# Ethernet.net
KiCad netlist of a schematic drawn in Altium Designer
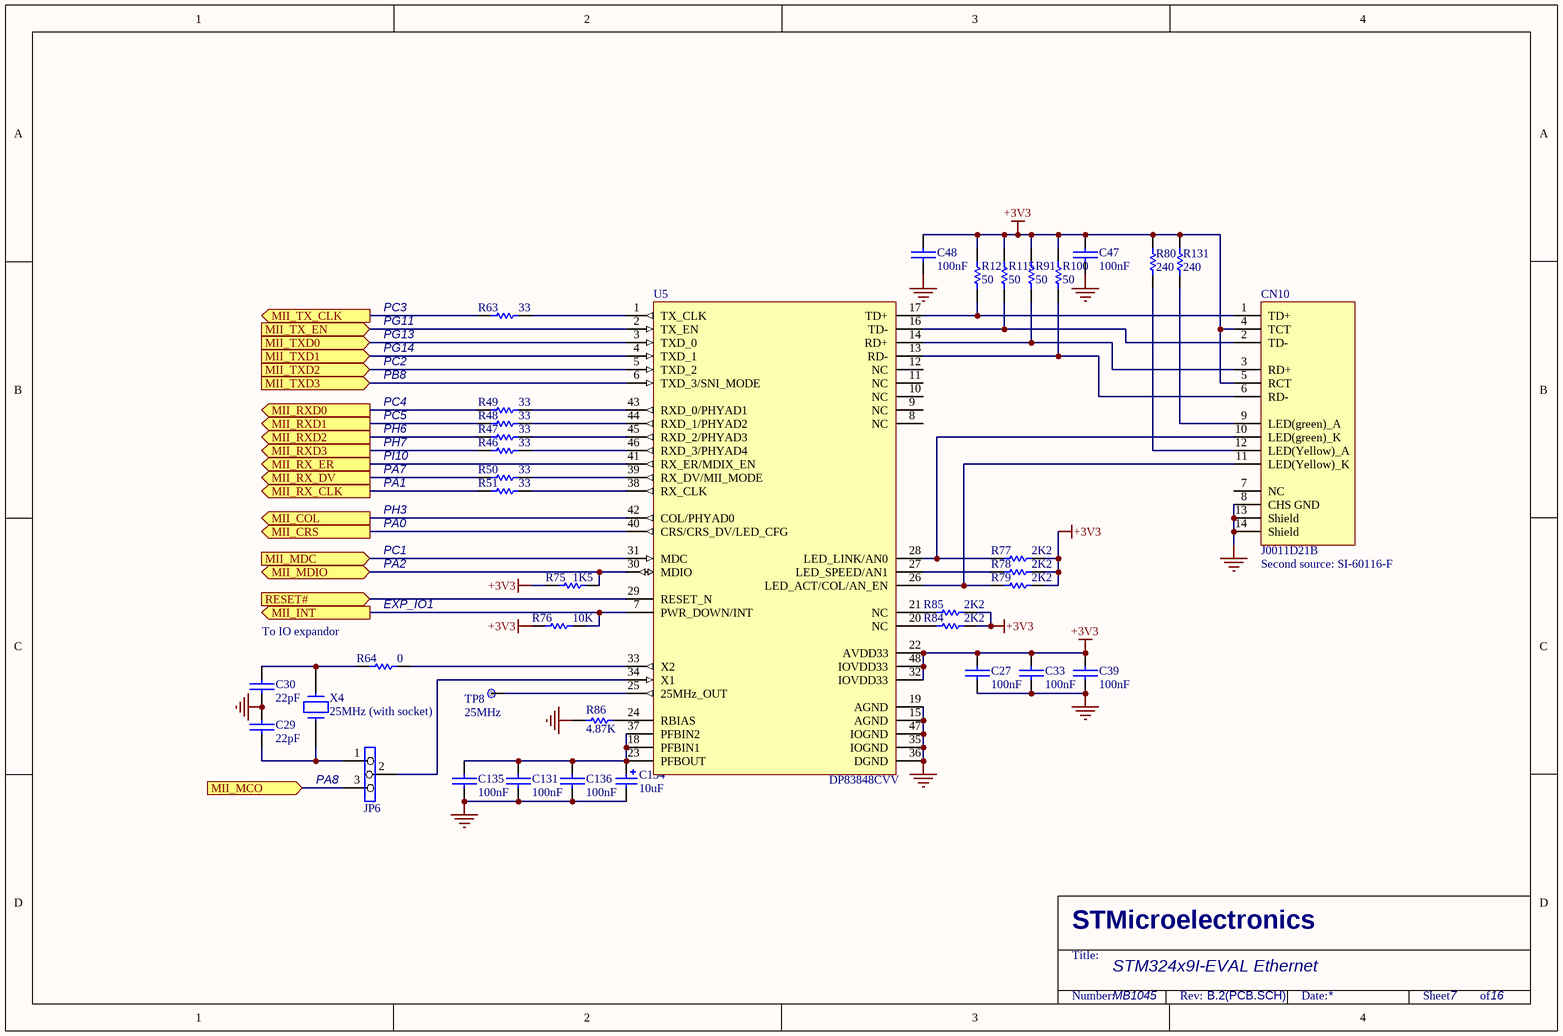
[diagram p0: Ethernet.SchDoc]

(export (version "E")
  (design (tool "Eeschema 10.0.6"))
  (components
    (comp (ref "C27")
      (value "100nF")
      (footprint "0603C")
      (description "Capacitor")
      (libsource (lib "*") (part "CAP"))
    )
    (comp (ref "C29")
      (value "22pF")
      (footprint "0603C")
      (description "Capacitor")
      (libsource (lib "*") (part "CAP"))
    )
    (comp (ref "C30")
      (value "22pF")
      (footprint "0603C")
      (description "Capacitor")
      (libsource (lib "*") (part "CAP"))
    )
    (comp (ref "C33")
      (value "100nF")
      (footprint "0603C")
      (description "Capacitor")
      (libsource (lib "*") (part "CAP"))
    )
    (comp (ref "C39")
      (value "100nF")
      (footprint "0603C")
      (description "Capacitor")
      (libsource (lib "*") (part "CAP"))
    )
    (comp (ref "C47")
      (value "100nF")
      (footprint "0603C")
      (description "Capacitor")
      (libsource (lib "*") (part "CAP"))
    )
    (comp (ref "C48")
      (value "100nF")
      (footprint "0603C")
      (description "Capacitor")
      (libsource (lib "*") (part "CAP"))
    )
    (comp (ref "C131")
      (value "100nF")
      (footprint "0603C")
      (description "Capacitor")
      (libsource (lib "*") (part "CAP"))
    )
    (comp (ref "C134")
      (value "10uF")
      (footprint "TAN-A")
      (description "Polarized Capacitor (Radial)")
      (fields (field (name "PUBLISHER") "Altium Limited"))
      (libsource (lib "Miscellaneous Devices") (part "Cap Pol1"))
    )
    (comp (ref "C135")
      (value "100nF")
      (footprint "0603C")
      (description "Capacitor")
      (libsource (lib "*") (part "CAP"))
    )
    (comp (ref "C136")
      (value "100nF")
      (footprint "0603C")
      (description "Capacitor")
      (libsource (lib "*") (part "CAP"))
    )
    (comp (ref "CN10")
      (value "J0011D21B")
      (footprint "RJ45_J0011D01BNL")
      (libsource (lib "MB784") (part "J0011D21B"))
    )
    (comp (ref "JP6") (value "~") (footprint "SIP3") (libsource (lib "STR910_SCHLIB") (part "Jumper3")))
    (comp (ref "R46")
      (value "33")
      (footprint "0603R")
      (description "Resistor")
      (fields (field (name "PUBLISHER") "Altium Limited"))
      (libsource (lib "Miscellaneous Devices") (part "Res1"))
    )
    (comp (ref "R47")
      (value "33")
      (footprint "0603R")
      (description "Resistor")
      (fields (field (name "PUBLISHER") "Altium Limited"))
      (libsource (lib "Miscellaneous Devices") (part "Res1"))
    )
    (comp (ref "R48")
      (value "33")
      (footprint "0603R")
      (description "Resistor")
      (fields (field (name "PUBLISHER") "Altium Limited"))
      (libsource (lib "Miscellaneous Devices") (part "Res1"))
    )
    (comp (ref "R49")
      (value "33")
      (footprint "0603R")
      (description "Resistor")
      (fields (field (name "PUBLISHER") "Altium Limited"))
      (libsource (lib "Miscellaneous Devices") (part "Res1"))
    )
    (comp (ref "R50")
      (value "33")
      (footprint "0603R")
      (description "Resistor")
      (fields (field (name "PUBLISHER") "Altium Limited"))
      (libsource (lib "Miscellaneous Devices") (part "Res1"))
    )
    (comp (ref "R51")
      (value "33")
      (footprint "0603R")
      (description "Resistor")
      (fields (field (name "PUBLISHER") "Altium Limited"))
      (libsource (lib "Miscellaneous Devices") (part "Res1"))
    )
    (comp (ref "R63")
      (value "33")
      (footprint "0603R")
      (description "Resistor")
      (fields (field (name "PUBLISHER") "Altium Limited"))
      (libsource (lib "Miscellaneous Devices") (part "Res1"))
    )
    (comp (ref "R64")
      (value "0")
      (footprint "0603R")
      (description "Resistor")
      (fields (field (name "PUBLISHER") "Altium Limited"))
      (libsource (lib "Miscellaneous Devices") (part "Res1"))
    )
    (comp (ref "R75")
      (value "1K5")
      (footprint "0603R")
      (description "Resistor")
      (fields (field (name "PUBLISHER") "Altium Limited"))
      (libsource (lib "Miscellaneous Devices") (part "Res1"))
    )
    (comp (ref "R76")
      (value "10K")
      (footprint "0603R")
      (description "Resistor")
      (fields (field (name "PUBLISHER") "Altium Limited"))
      (libsource (lib "Miscellaneous Devices") (part "Res1"))
    )
    (comp (ref "R77")
      (value "2K2")
      (footprint "0603R")
      (description "Resistor")
      (fields (field (name "PUBLISHER") "Altium Limited"))
      (libsource (lib "Miscellaneous Devices") (part "Res1"))
    )
    (comp (ref "R78")
      (value "2K2")
      (footprint "0603R")
      (description "Resistor")
      (fields (field (name "PUBLISHER") "Altium Limited"))
      (libsource (lib "Miscellaneous Devices") (part "Res1"))
    )
    (comp (ref "R79")
      (value "2K2")
      (footprint "0603R")
      (description "Resistor")
      (fields (field (name "PUBLISHER") "Altium Limited"))
      (libsource (lib "Miscellaneous Devices") (part "Res1"))
    )
    (comp (ref "R80")
      (value "240")
      (footprint "0603R")
      (description "Resistor")
      (fields (field (name "PUBLISHER") "Altium Limited"))
      (libsource (lib "Miscellaneous Devices") (part "Res1"))
    )
    (comp (ref "R84")
      (value "2K2")
      (footprint "0603R")
      (description "Resistor")
      (fields (field (name "PUBLISHER") "Altium Limited"))
      (libsource (lib "Miscellaneous Devices") (part "Res1"))
    )
    (comp (ref "R85")
      (value "2K2")
      (footprint "0603R")
      (description "Resistor")
      (fields (field (name "PUBLISHER") "Altium Limited"))
      (libsource (lib "Miscellaneous Devices") (part "Res1"))
    )
    (comp (ref "R86")
      (value "4.87K")
      (footprint "0603R")
      (description "Resistor")
      (fields (field (name "PUBLISHER") "Altium Limited"))
      (libsource (lib "Miscellaneous Devices") (part "Res1"))
    )
    (comp (ref "R91")
      (value "50")
      (footprint "0603R")
      (description "Resistor")
      (fields (field (name "PUBLISHER") "Altium Limited"))
      (libsource (lib "Miscellaneous Devices") (part "Res1"))
    )
    (comp (ref "R100")
      (value "50")
      (footprint "0603R")
      (description "Resistor")
      (fields (field (name "PUBLISHER") "Altium Limited"))
      (libsource (lib "Miscellaneous Devices") (part "Res1"))
    )
    (comp (ref "R115")
      (value "50")
      (footprint "0603R")
      (description "Resistor")
      (fields (field (name "PUBLISHER") "Altium Limited"))
      (libsource (lib "Miscellaneous Devices") (part "Res1"))
    )
    (comp (ref "R121")
      (value "50")
      (footprint "0603R")
      (description "Resistor")
      (fields (field (name "PUBLISHER") "Altium Limited"))
      (libsource (lib "Miscellaneous Devices") (part "Res1"))
    )
    (comp (ref "R131")
      (value "240")
      (footprint "0603R")
      (description "Resistor")
      (fields (field (name "PUBLISHER") "Altium Limited"))
      (libsource (lib "Miscellaneous Devices") (part "Res1"))
    )
    (comp (ref "TP8") (value "25MHz") (footprint "TP") (libsource (lib "*") (part "TP")))
    (comp (ref "U5")
      (value "DP83848CVV")
      (footprint "LQFP48_0R5_9X9")
      (libsource (lib "MB784") (part "DP83848CVV"))
    )
    (comp (ref "X4")
      (value "25MHz (with socket)")
      (footprint "XTAL_socket")
      (description "Crystal")
      (libsource (lib "*") (part "CRYSTAL"))
    )
  )
  (nets
    (net (code "1") (name "+3V3") (class "Default")
      (node (ref "C27") (pin "1") (pinfunction "1_1") (pintype "passive"))
      (node (ref "C33") (pin "2") (pinfunction "2_2") (pintype "passive"))
      (node (ref "C39") (pin "2") (pinfunction "2_2") (pintype "passive"))
      (node (ref "C47") (pin "2") (pinfunction "2_2") (pintype "passive"))
      (node (ref "C48") (pin "2") (pinfunction "2_2") (pintype "passive"))
      (node (ref "CN10") (pin "4") (pinfunction "TCT_4") (pintype "passive"))
      (node (ref "CN10") (pin "5") (pinfunction "RCT_5") (pintype "passive"))
      (node (ref "R100") (pin "1") (pinfunction "1_1") (pintype "passive"))
      (node (ref "R115") (pin "1") (pinfunction "1_1") (pintype "passive"))
      (node (ref "R121") (pin "1") (pinfunction "1_1") (pintype "passive"))
      (node (ref "R131") (pin "2") (pinfunction "2_2") (pintype "passive"))
      (node (ref "R75") (pin "2") (pinfunction "2_2") (pintype "passive"))
      (node (ref "R76") (pin "1") (pinfunction "1_1") (pintype "passive"))
      (node (ref "R77") (pin "2") (pinfunction "2_2") (pintype "passive"))
      (node (ref "R78") (pin "2") (pinfunction "2_2") (pintype "passive"))
      (node (ref "R79") (pin "2") (pinfunction "2_2") (pintype "passive"))
      (node (ref "R80") (pin "2") (pinfunction "2_2") (pintype "passive"))
      (node (ref "R84") (pin "2") (pinfunction "2_2") (pintype "passive"))
      (node (ref "R85") (pin "2") (pinfunction "2_2") (pintype "passive"))
      (node (ref "R91") (pin "1") (pinfunction "1_1") (pintype "passive"))
      (node (ref "U5") (pin "22") (pinfunction "AVDD33_22") (pintype "passive"))
      (node (ref "U5") (pin "32") (pinfunction "IOVDD33_32") (pintype "passive"))
      (node (ref "U5") (pin "48") (pinfunction "IOVDD33_48") (pintype "passive"))
    )
    (net (code "2") (name "/MII_COL") (class "Default")
      (node (ref "U5") (pin "42") (pinfunction "COL/PHYAD0_42") (pintype "output"))
    )
    (net (code "3") (name "/MII_CRS") (class "Default")
      (node (ref "U5") (pin "40") (pinfunction "CRS/CRS_DV/LED_CFG_40") (pintype "output"))
    )
    (net (code "4") (name "/MII_INT") (class "Default")
      (node (ref "R76") (pin "2") (pinfunction "2_2") (pintype "passive"))
      (node (ref "U5") (pin "7") (pinfunction "PWR_DOWN/INT_7") (pintype "passive"))
    )
    (net (code "5") (name "/MII_MCO") (class "Default") (node (ref "JP6") (pin "3") (pintype "passive")))
    (net (code "6") (name "/MII_MDC") (class "Default")
      (node (ref "U5") (pin "31") (pinfunction "MDC_31") (pintype "input"))
    )
    (net (code "7") (name "/MII_MDIO") (class "Default")
      (node (ref "R75") (pin "1") (pinfunction "1_1") (pintype "passive"))
      (node (ref "U5") (pin "30") (pinfunction "MDIO_30") (pintype "bidirectional"))
    )
    (net (code "8") (name "/MII_RXD0") (class "Default")
      (node (ref "R49") (pin "2") (pinfunction "2_2") (pintype "passive"))
    )
    (net (code "9") (name "/MII_RXD1") (class "Default")
      (node (ref "R48") (pin "2") (pinfunction "2_2") (pintype "passive"))
    )
    (net (code "10") (name "/MII_RXD2") (class "Default")
      (node (ref "R47") (pin "2") (pinfunction "2_2") (pintype "passive"))
    )
    (net (code "11") (name "/MII_RXD3") (class "Default")
      (node (ref "R46") (pin "2") (pinfunction "2_2") (pintype "passive"))
    )
    (net (code "12") (name "/MII_RX_CLK") (class "Default")
      (node (ref "R51") (pin "2") (pinfunction "2_2") (pintype "passive"))
    )
    (net (code "13") (name "/MII_RX_DV") (class "Default")
      (node (ref "R50") (pin "2") (pinfunction "2_2") (pintype "passive"))
    )
    (net (code "14") (name "/MII_RX_ER") (class "Default")
      (node (ref "U5") (pin "41") (pinfunction "RX_ER/MDIX_EN_41") (pintype "output"))
    )
    (net (code "15") (name "/MII_TXD0") (class "Default")
      (node (ref "U5") (pin "3") (pinfunction "TXD_0_3") (pintype "input"))
    )
    (net (code "16") (name "/MII_TXD1") (class "Default")
      (node (ref "U5") (pin "4") (pinfunction "TXD_1_4") (pintype "input"))
    )
    (net (code "17") (name "/MII_TXD2") (class "Default")
      (node (ref "U5") (pin "5") (pinfunction "TXD_2_5") (pintype "input"))
    )
    (net (code "18") (name "/MII_TXD3") (class "Default")
      (node (ref "U5") (pin "6") (pinfunction "TXD_3/SNI_MODE_6") (pintype "input"))
    )
    (net (code "19") (name "/MII_TX_CLK") (class "Default")
      (node (ref "R63") (pin "2") (pinfunction "2_2") (pintype "passive"))
    )
    (net (code "20") (name "/MII_TX_EN") (class "Default")
      (node (ref "U5") (pin "2") (pinfunction "TX_EN_2") (pintype "input"))
    )
    (net (code "21") (name "/RESET#") (class "Default")
      (node (ref "U5") (pin "29") (pinfunction "RESET_N_29") (pintype "passive"))
    )
    (net (code "22") (name "GND") (class "Default")
      (node (ref "C131") (pin "1") (pinfunction "1_1") (pintype "passive"))
      (node (ref "C134") (pin "2") (pinfunction "2_2") (pintype "passive"))
      (node (ref "C135") (pin "2") (pinfunction "2_2") (pintype "passive"))
      (node (ref "C136") (pin "1") (pinfunction "1_1") (pintype "passive"))
      (node (ref "C27") (pin "2") (pinfunction "2_2") (pintype "passive"))
      (node (ref "C29") (pin "2") (pinfunction "2_2") (pintype "passive"))
      (node (ref "C30") (pin "1") (pinfunction "1_1") (pintype "passive"))
      (node (ref "C33") (pin "1") (pinfunction "1_1") (pintype "passive"))
      (node (ref "C39") (pin "1") (pinfunction "1_1") (pintype "passive"))
      (node (ref "C47") (pin "1") (pinfunction "1_1") (pintype "passive"))
      (node (ref "C48") (pin "1") (pinfunction "1_1") (pintype "passive"))
      (node (ref "CN10") (pin "13") (pinfunction "Shield_13") (pintype "passive"))
      (node (ref "CN10") (pin "14") (pinfunction "Shield_14") (pintype "passive"))
      (node (ref "CN10") (pin "8") (pinfunction "CHS_GND_8") (pintype "passive"))
      (node (ref "R86") (pin "1") (pinfunction "1_1") (pintype "passive"))
      (node (ref "U5") (pin "15") (pinfunction "AGND_15") (pintype "passive"))
      (node (ref "U5") (pin "19") (pinfunction "AGND_19") (pintype "passive"))
      (node (ref "U5") (pin "35") (pinfunction "IOGND_35") (pintype "passive"))
      (node (ref "U5") (pin "36") (pinfunction "DGND_36") (pintype "passive"))
      (node (ref "U5") (pin "47") (pinfunction "IOGND_47") (pintype "passive"))
    )
    (net (code "23") (name "Net-(C29-Pad1)") (class "Default")
      (node (ref "C29") (pin "1") (pinfunction "1_1") (pintype "passive"))
      (node (ref "JP6") (pin "1") (pintype "passive"))
      (node (ref "X4") (pin "1") (pinfunction "1_1") (pintype "passive"))
    )
    (net (code "24") (name "Net-(C30-Pad2)") (class "Default")
      (node (ref "C30") (pin "2") (pinfunction "2_2") (pintype "passive"))
      (node (ref "R64") (pin "2") (pinfunction "2_2") (pintype "passive"))
      (node (ref "X4") (pin "2") (pinfunction "2_2") (pintype "passive"))
    )
    (net (code "25") (name "Net-(CN10-LED(Yellow)_A)") (class "Default")
      (node (ref "CN10") (pin "12") (pinfunction "LED(Yellow)_A_12") (pintype "passive"))
      (node (ref "R80") (pin "1") (pinfunction "1_1") (pintype "passive"))
    )
    (net (code "26") (name "Net-(CN10-LED(Yellow)_K)") (class "Default")
      (node (ref "CN10") (pin "11") (pinfunction "LED(Yellow)_K_11") (pintype "passive"))
      (node (ref "R79") (pin "1") (pinfunction "1_1") (pintype "passive"))
      (node (ref "U5") (pin "26") (pinfunction "LED_ACT/COL/AN_EN_26") (pintype "passive"))
    )
    (net (code "27") (name "Net-(CN10-LED(green)_A)") (class "Default")
      (node (ref "CN10") (pin "9") (pinfunction "LED(green)_A_9") (pintype "passive"))
      (node (ref "R131") (pin "1") (pinfunction "1_1") (pintype "passive"))
    )
    (net (code "28") (name "Net-(CN10-LED(green)_K)") (class "Default")
      (node (ref "CN10") (pin "10") (pinfunction "LED(green)_K_10") (pintype "passive"))
      (node (ref "R77") (pin "1") (pinfunction "1_1") (pintype "passive"))
      (node (ref "U5") (pin "28") (pinfunction "LED_LINK/AN0_28") (pintype "passive"))
    )
    (net (code "29") (name "Net-(CN10-RD+)") (class "Default")
      (node (ref "CN10") (pin "3") (pinfunction "RD+_3") (pintype "passive"))
      (node (ref "R91") (pin "2") (pinfunction "2_2") (pintype "passive"))
      (node (ref "U5") (pin "14") (pinfunction "RD+_14") (pintype "passive"))
    )
    (net (code "30") (name "Net-(CN10-RD-)") (class "Default")
      (node (ref "CN10") (pin "6") (pinfunction "RD-_6") (pintype "passive"))
      (node (ref "R100") (pin "2") (pinfunction "2_2") (pintype "passive"))
      (node (ref "U5") (pin "13") (pinfunction "RD-_13") (pintype "passive"))
    )
    (net (code "31") (name "Net-(CN10-TD+)") (class "Default")
      (node (ref "CN10") (pin "1") (pinfunction "TD+_1") (pintype "passive"))
      (node (ref "R121") (pin "2") (pinfunction "2_2") (pintype "passive"))
      (node (ref "U5") (pin "17") (pinfunction "TD+_17") (pintype "passive"))
    )
    (net (code "32") (name "Net-(CN10-TD-)") (class "Default")
      (node (ref "CN10") (pin "2") (pinfunction "TD-_2") (pintype "passive"))
      (node (ref "R115") (pin "2") (pinfunction "2_2") (pintype "passive"))
      (node (ref "U5") (pin "16") (pinfunction "TD-_16") (pintype "passive"))
    )
    (net (code "33") (name "Net-(R84-Pad1)") (class "Default")
      (node (ref "R84") (pin "1") (pinfunction "1_1") (pintype "passive"))
      (node (ref "U5") (pin "20") (pinfunction "NC_20") (pintype "passive"))
    )
    (net (code "34") (name "Net-(R85-Pad1)") (class "Default")
      (node (ref "R85") (pin "1") (pinfunction "1_1") (pintype "passive"))
      (node (ref "U5") (pin "21") (pinfunction "NC_21") (pintype "passive"))
    )
    (net (code "35") (name "Net-(U5-25MHz_OUT)") (class "Default")
      (node (ref "TP8") (pin "1") (pinfunction "1_1") (pintype "passive"))
      (node (ref "U5") (pin "25") (pinfunction "25MHz_OUT_25") (pintype "output"))
    )
    (net (code "36") (name "Net-(U5-LED_SPEED{slash}AN1)") (class "Default")
      (node (ref "R78") (pin "1") (pinfunction "1_1") (pintype "passive"))
      (node (ref "U5") (pin "27") (pinfunction "LED_SPEED/AN1_27") (pintype "passive"))
    )
    (net (code "37") (name "Net-(U5-PFBIN1)") (class "Default")
      (node (ref "C131") (pin "2") (pinfunction "2_2") (pintype "passive"))
      (node (ref "C134") (pin "1") (pinfunction "1_1") (pintype "passive"))
      (node (ref "C135") (pin "1") (pinfunction "1_1") (pintype "passive"))
      (node (ref "C136") (pin "2") (pinfunction "2_2") (pintype "passive"))
      (node (ref "U5") (pin "18") (pinfunction "PFBIN1_18") (pintype "passive"))
      (node (ref "U5") (pin "23") (pinfunction "PFBOUT_23") (pintype "passive"))
      (node (ref "U5") (pin "37") (pinfunction "PFBIN2_37") (pintype "passive"))
    )
    (net (code "38") (name "Net-(U5-RBIAS)") (class "Default")
      (node (ref "R86") (pin "2") (pinfunction "2_2") (pintype "passive"))
      (node (ref "U5") (pin "24") (pinfunction "RBIAS_24") (pintype "passive"))
    )
    (net (code "39") (name "Net-(U5-RXD_0{slash}PHYAD1)") (class "Default")
      (node (ref "R49") (pin "1") (pinfunction "1_1") (pintype "passive"))
      (node (ref "U5") (pin "43") (pinfunction "RXD_0/PHYAD1_43") (pintype "output"))
    )
    (net (code "40") (name "Net-(U5-RXD_1{slash}PHYAD2)") (class "Default")
      (node (ref "R48") (pin "1") (pinfunction "1_1") (pintype "passive"))
      (node (ref "U5") (pin "44") (pinfunction "RXD_1/PHYAD2_44") (pintype "output"))
    )
    (net (code "41") (name "Net-(U5-RXD_2{slash}PHYAD3)") (class "Default")
      (node (ref "R47") (pin "1") (pinfunction "1_1") (pintype "passive"))
      (node (ref "U5") (pin "45") (pinfunction "RXD_2/PHYAD3_45") (pintype "output"))
    )
    (net (code "42") (name "Net-(U5-RXD_3{slash}PHYAD4)") (class "Default")
      (node (ref "R46") (pin "1") (pinfunction "1_1") (pintype "passive"))
      (node (ref "U5") (pin "46") (pinfunction "RXD_3/PHYAD4_46") (pintype "output"))
    )
    (net (code "43") (name "Net-(U5-RX_CLK)") (class "Default")
      (node (ref "R51") (pin "1") (pinfunction "1_1") (pintype "passive"))
      (node (ref "U5") (pin "38") (pinfunction "RX_CLK_38") (pintype "output"))
    )
    (net (code "44") (name "Net-(U5-RX_DV{slash}MII_MODE)") (class "Default")
      (node (ref "R50") (pin "1") (pinfunction "1_1") (pintype "passive"))
      (node (ref "U5") (pin "39") (pinfunction "RX_DV/MII_MODE_39") (pintype "output"))
    )
    (net (code "45") (name "Net-(U5-TX_CLK)") (class "Default")
      (node (ref "R63") (pin "1") (pinfunction "1_1") (pintype "passive"))
      (node (ref "U5") (pin "1") (pinfunction "TX_CLK_1") (pintype "output"))
    )
    (net (code "46") (name "Net-(U5-X1)") (class "Default")
      (node (ref "JP6") (pin "2") (pintype "passive"))
      (node (ref "U5") (pin "34") (pinfunction "X1_34") (pintype "input"))
    )
    (net (code "47") (name "Net-(U5-X2)") (class "Default")
      (node (ref "R64") (pin "1") (pinfunction "1_1") (pintype "passive"))
      (node (ref "U5") (pin "33") (pinfunction "X2_33") (pintype "output"))
    )
    (net (code "48") (name "unconnected-(CN10-NC-Pad7)") (class "Default")
      (node (ref "CN10") (pin "7") (pinfunction "NC_7") (pintype "passive"))
    )
    (net (code "49") (name "unconnected-(U5-NC-Pad8)") (class "Default")
      (node (ref "U5") (pin "8") (pinfunction "NC_8") (pintype "passive"))
    )
    (net (code "50") (name "unconnected-(U5-NC-Pad9)") (class "Default")
      (node (ref "U5") (pin "9") (pinfunction "NC_9") (pintype "passive"))
    )
    (net (code "51") (name "unconnected-(U5-NC-Pad10)") (class "Default")
      (node (ref "U5") (pin "10") (pinfunction "NC_10") (pintype "passive"))
    )
    (net (code "52") (name "unconnected-(U5-NC-Pad11)") (class "Default")
      (node (ref "U5") (pin "11") (pinfunction "NC_11") (pintype "passive"))
    )
    (net (code "53") (name "unconnected-(U5-NC-Pad12)") (class "Default")
      (node (ref "U5") (pin "12") (pinfunction "NC_12") (pintype "passive"))
    )
  )
)
